# schematic.net
KiCad netlist of a schematic drawn in EasyEDA
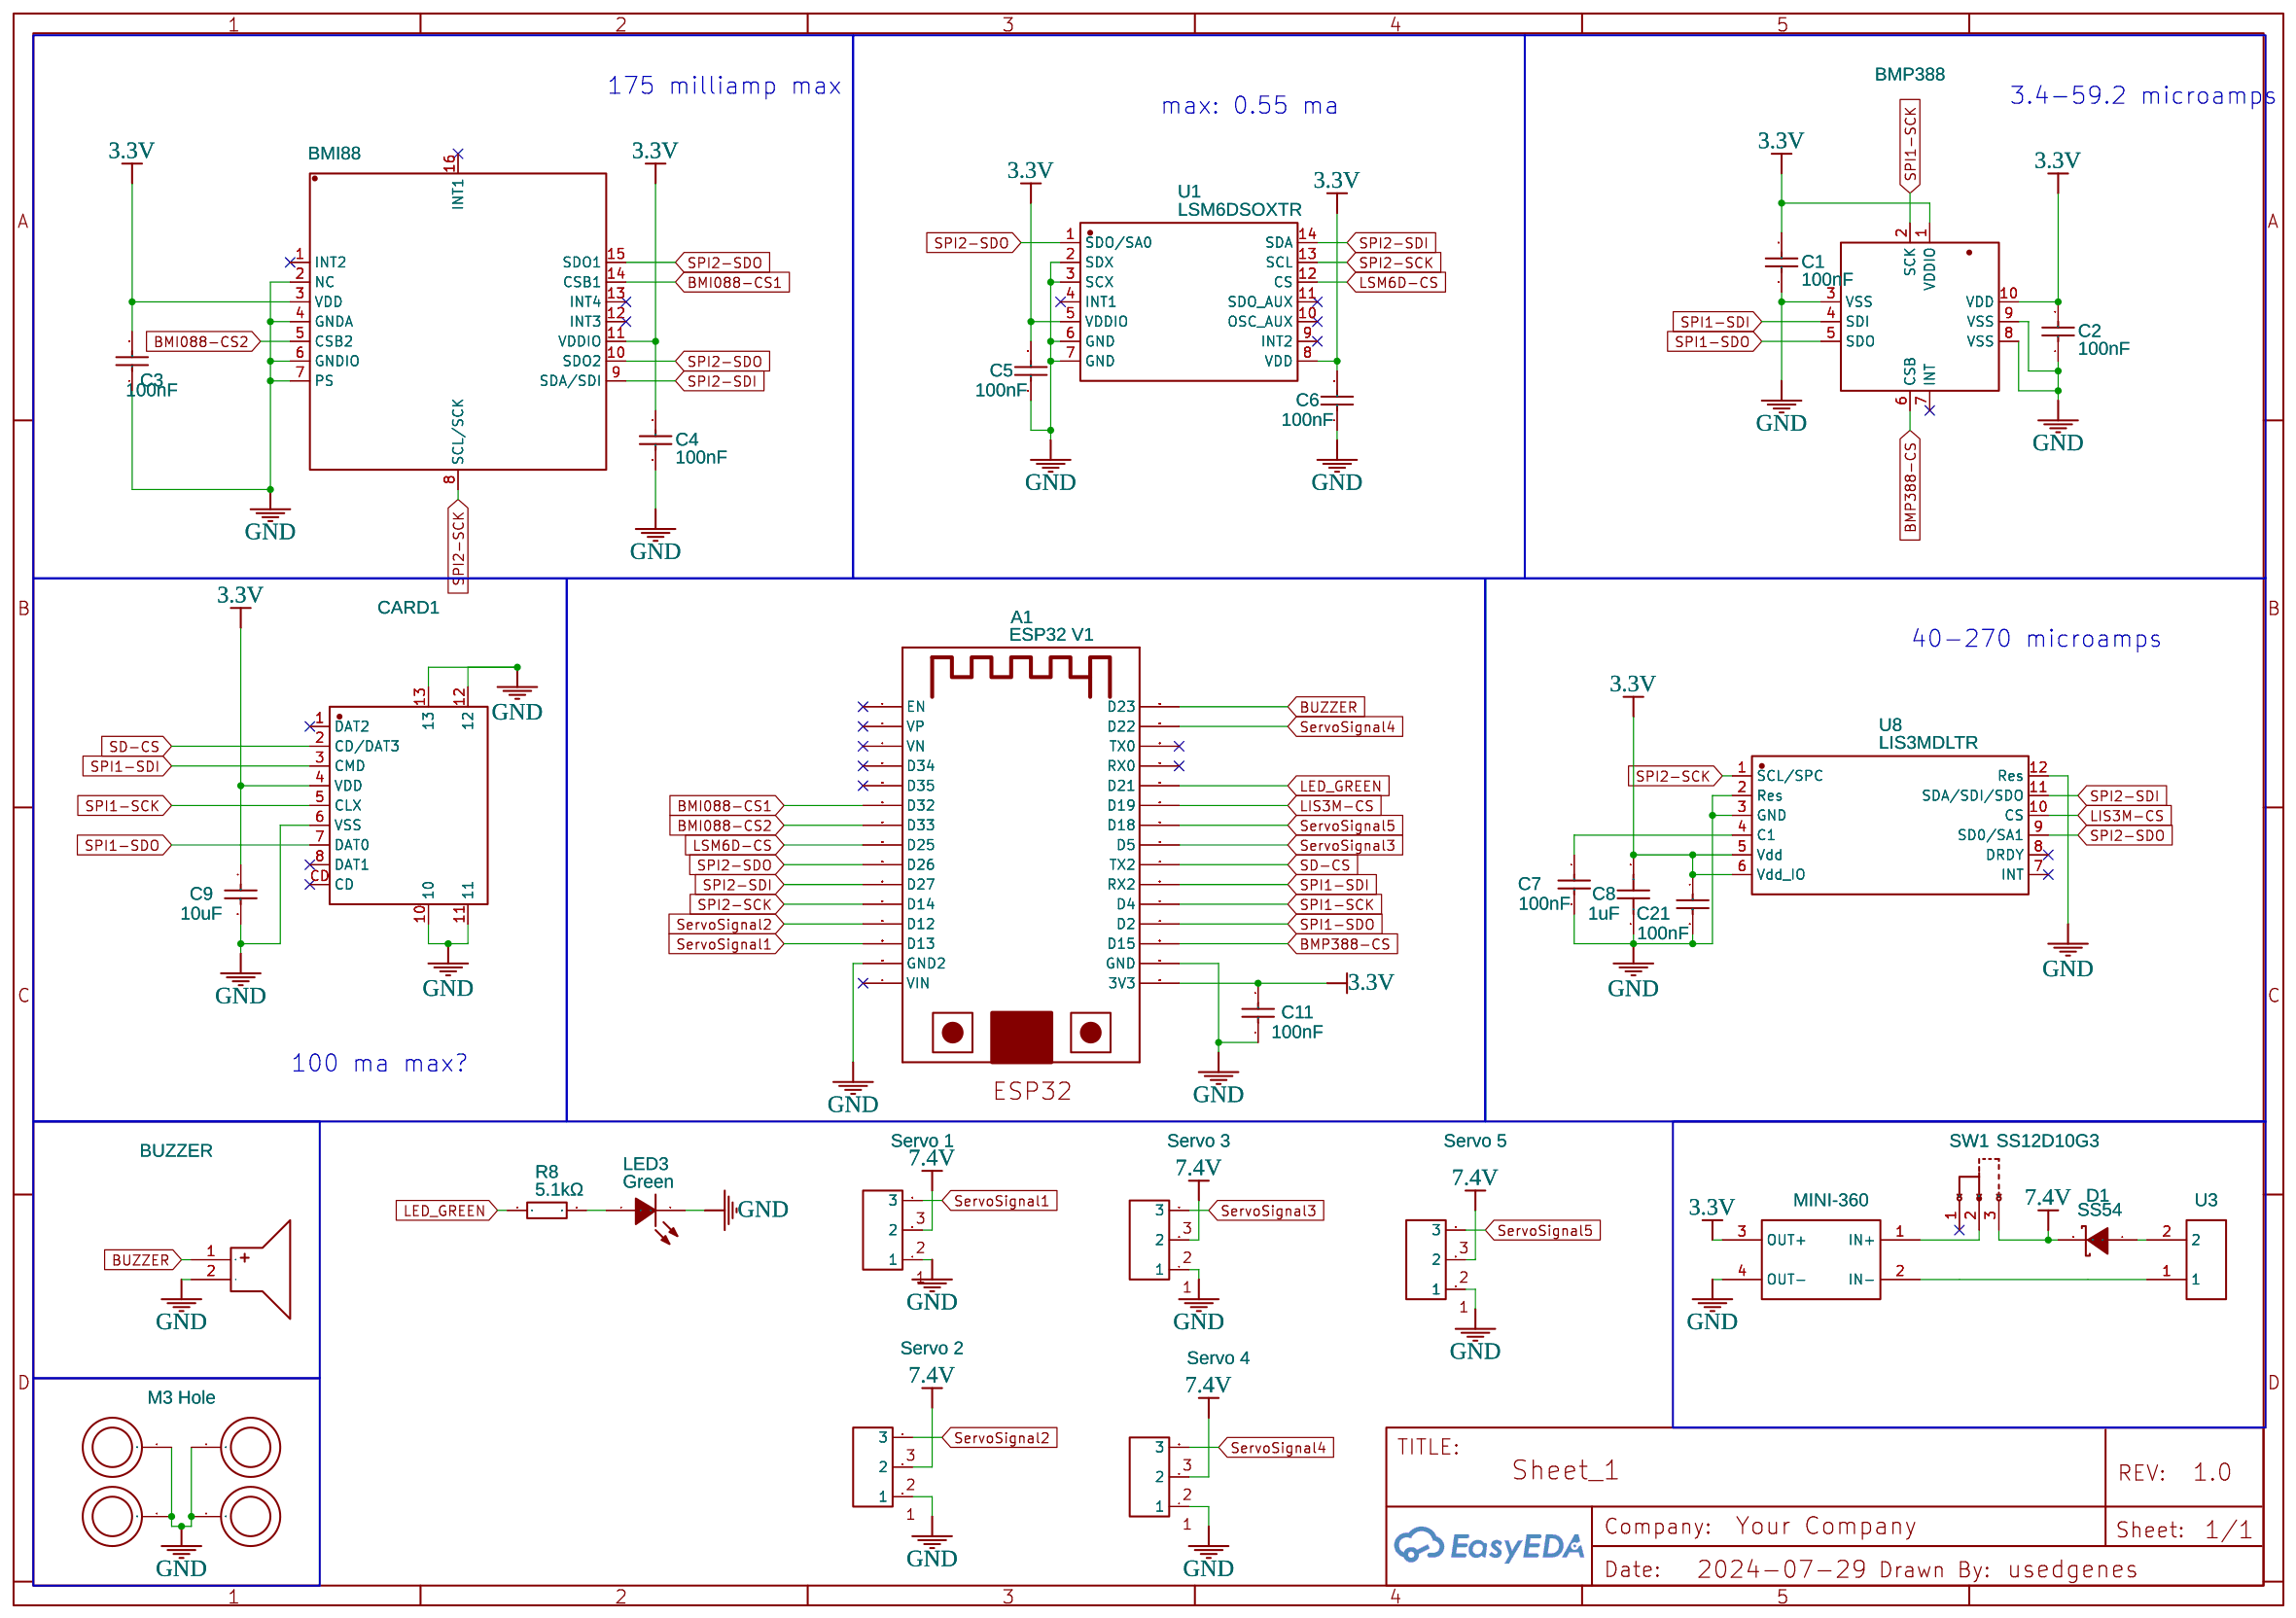
[diagram p0: schematic sheet]

(export (version "E")
  (design (tool "Eeschema 10.0.6"))
  (components
    (comp (ref "A1") (value "ESP32 V1") (libsource (lib "") (part "ESP32-DEVKIT-V1-30PIN")))
    (comp (ref "BMI88")
      (value "BMI088")
      (fields (field (name "Manufacturer") "Bosch(博世)"))
      (libsource (lib "") (part "BMI088"))
    )
    (comp (ref "BMP388")
      (value "BMP388")
      (fields (field (name "Manufacturer") "Bosch(博世)"))
      (libsource (lib "") (part "BMP388"))
    )
    (comp (ref "BUZZER")
      (value "4000Hz")
      (fields
        (field (name "Manufacturer Part") "SKY-1475-0540-45P7.6")
        (field (name "Manufacturer") "S&S(海旭)")
      )
      (libsource (lib "") (part "SKY-1475-0540-45P7.6"))
    )
    (comp (ref "C1")
      (value "100nF")
      (fields
        (field (name "Manufacturer Part") "CL05B104KO5NNNC")
        (field (name "Manufacturer") "SAMSUNG(三星)")
      )
      (libsource (lib "") (part "CL05B104KO5NNNC"))
    )
    (comp (ref "C2")
      (value "100nF")
      (fields
        (field (name "Manufacturer Part") "CL05B104KO5NNNC")
        (field (name "Manufacturer") "SAMSUNG(三星)")
      )
      (libsource (lib "") (part "CL05B104KO5NNNC"))
    )
    (comp (ref "C3")
      (value "100nF")
      (fields
        (field (name "Manufacturer Part") "CL05B104KO5NNNC")
        (field (name "Manufacturer") "SAMSUNG(三星)")
      )
      (libsource (lib "") (part "CL05B104KO5NNNC"))
    )
    (comp (ref "C4")
      (value "100nF")
      (fields
        (field (name "Manufacturer Part") "CL05B104KO5NNNC")
        (field (name "Manufacturer") "SAMSUNG(三星)")
      )
      (libsource (lib "") (part "CL05B104KO5NNNC"))
    )
    (comp (ref "C5")
      (value "100nF")
      (fields
        (field (name "Manufacturer Part") "CL05B104KO5NNNC")
        (field (name "Manufacturer") "SAMSUNG(三星)")
      )
      (libsource (lib "") (part "CL05B104KO5NNNC"))
    )
    (comp (ref "C6")
      (value "100nF")
      (fields
        (field (name "Manufacturer Part") "CL05B104KO5NNNC")
        (field (name "Manufacturer") "SAMSUNG(三星)")
      )
      (libsource (lib "") (part "CL05B104KO5NNNC"))
    )
    (comp (ref "C7")
      (value "100nF")
      (fields
        (field (name "Manufacturer Part") "CL05B104KO5NNNC")
        (field (name "Manufacturer") "SAMSUNG(三星)")
      )
      (libsource (lib "") (part "CL05B104KO5NNNC_1"))
    )
    (comp (ref "C8")
      (value "1uF")
      (fields
        (field (name "Manufacturer Part") "CL05A105KA5NQNC")
        (field (name "Manufacturer") "SAMSUNG(三星)")
      )
      (libsource (lib "") (part "CL05A105KA5NQNC"))
    )
    (comp (ref "C9")
      (value "10uF")
      (fields
        (field (name "Manufacturer Part") "CL05A106MQ5NUNC")
        (field (name "Manufacturer") "SAMSUNG(三星)")
      )
      (libsource (lib "") (part "CL05A106MQ5NUNC"))
    )
    (comp (ref "C11")
      (value "100nF")
      (fields
        (field (name "Manufacturer Part") "CL05B104KO5NNNC")
        (field (name "Manufacturer") "SAMSUNG(三星)")
      )
      (libsource (lib "") (part "CL05B104KO5NNNC"))
    )
    (comp (ref "C21")
      (value "100nF")
      (fields
        (field (name "Manufacturer Part") "CL05B104KO5NNNC")
        (field (name "Manufacturer") "SAMSUNG(三星)")
      )
      (libsource (lib "") (part "CL05B104KO5NNNC_1"))
    )
    (comp (ref "CARD1")
      (value "TF PUSH")
      (fields (field (name "Manufacturer") "SHOU HAN(首韩)"))
      (libsource (lib "") (part "TF PUSH"))
    )
    (comp (ref "D1")
      (value "SS54")
      (fields (field (name "Manufacturer") "MDD(辰达半导体)"))
      (libsource (lib "") (part "SS54_C22452"))
    )
    (comp (ref "H1") (value "M3 Hole") (libsource (lib "") (part "3MM_HOLE_1")))
    (comp (ref "H2") (value "3MM_HOLE") (libsource (lib "") (part "3MM_HOLE")))
    (comp (ref "H3") (value "3MM_HOLE") (libsource (lib "") (part "3MM_HOLE_1")))
    (comp (ref "H4") (value "3MM_HOLE") (libsource (lib "") (part "3MM_HOLE")))
    (comp (ref "LED3")
      (value "Green")
      (fields (field (name "Manufacturer Part") "KT-0805G") (field (name "Manufacturer") "KENTO"))
      (libsource (lib "") (part "0805G (Green)"))
    )
    (comp (ref "MINI-360") (value "MINI-360") (libsource (lib "") (part "MINI-360")))
    (comp (ref "P1")
      (value "Servo 2")
      (fields
        (field (name "Manufacturer Part") "Female headerHDR1X8-2.54")
        (field (name "Manufacturer") "BOOMELE")
      )
      (libsource (lib "") (part "HEADER PAD 3X RMM COPY"))
    )
    (comp (ref "P2")
      (value "Servo 1")
      (fields
        (field (name "Manufacturer Part") "Female headerHDR1X8-2.54")
        (field (name "Manufacturer") "BOOMELE")
      )
      (libsource (lib "") (part "HEADER PAD 3X RMM COPY"))
    )
    (comp (ref "P3")
      (value "Servo 3")
      (fields
        (field (name "Manufacturer Part") "Female headerHDR1X8-2.54")
        (field (name "Manufacturer") "BOOMELE")
      )
      (libsource (lib "") (part "HEADER PAD 3X RMM COPY"))
    )
    (comp (ref "P4")
      (value "Servo 5")
      (fields
        (field (name "Manufacturer Part") "Female headerHDR1X8-2.54")
        (field (name "Manufacturer") "BOOMELE")
      )
      (libsource (lib "") (part "HEADER PAD 3X RMM COPY"))
    )
    (comp (ref "P5")
      (value "Servo 4")
      (fields
        (field (name "Manufacturer Part") "Female headerHDR1X8-2.54")
        (field (name "Manufacturer") "BOOMELE")
      )
      (libsource (lib "") (part "HEADER PAD 3X RMM COPY"))
    )
    (comp (ref "R8")
      (value "5.1kΩ")
      (fields
        (field (name "Manufacturer Part") "0402WGF5101TCE")
        (field (name "Manufacturer") "UNI-ROYAL(厚声)")
      )
      (libsource (lib "") (part "0402WGF5101TCE"))
    )
    (comp (ref "SW1")
      (value "SS12D10G3")
      (fields (field (name "Manufacturer") "SHOU HAN(首韩)"))
      (libsource (lib "") (part "SS12D10G3"))
    )
    (comp (ref "U1")
      (value "LSM6DSOXTR")
      (fields (field (name "Manufacturer") "ST(意法半导体)"))
      (libsource (lib "") (part "LSM6DSOXTR"))
    )
    (comp (ref "U3") (value "Power Pins") (libsource (lib "") (part "1X2")))
    (comp (ref "U8")
      (value "LIS3MDLTR")
      (fields (field (name "Manufacturer") "ST(意法半导体)"))
      (libsource (lib "") (part "LIS3MDLTR"))
    )
  )
  (nets
    (net (code "1") (name "3.3V") (class "Default")
      (node (ref "A1") (pin "3V3") (pinfunction "3V3_3V3") (pintype "unspecified"))
      (node (ref "BMI88") (pin "11") (pinfunction "VDDIO_11") (pintype "unspecified"))
      (node (ref "BMI88") (pin "3") (pinfunction "VDD_3") (pintype "unspecified"))
      (node (ref "BMP388") (pin "1") (pinfunction "VDDIO_1") (pintype "unspecified"))
      (node (ref "BMP388") (pin "10") (pinfunction "VDD_10") (pintype "unspecified"))
      (node (ref "C1") (pin "2") (pinfunction "2_2") (pintype "input"))
      (node (ref "C11") (pin "2") (pinfunction "2_2") (pintype "input"))
      (node (ref "C2") (pin "2") (pinfunction "2_2") (pintype "input"))
      (node (ref "C21") (pin "1") (pinfunction "1_1") (pintype "input"))
      (node (ref "C3") (pin "2") (pinfunction "2_2") (pintype "input"))
      (node (ref "C4") (pin "2") (pinfunction "2_2") (pintype "input"))
      (node (ref "C5") (pin "2") (pinfunction "2_2") (pintype "input"))
      (node (ref "C6") (pin "2") (pinfunction "2_2") (pintype "input"))
      (node (ref "C8") (pin "2") (pinfunction "2_2") (pintype "unspecified"))
      (node (ref "C9") (pin "1") (pinfunction "1_1") (pintype "input"))
      (node (ref "CARD1") (pin "4") (pinfunction "VDD_4") (pintype "unspecified"))
      (node (ref "MINI-360") (pin "3") (pinfunction "OUT+_3") (pintype "unspecified"))
      (node (ref "U1") (pin "5") (pinfunction "VDDIO_5") (pintype "unspecified"))
      (node (ref "U1") (pin "8") (pinfunction "VDD_8") (pintype "unspecified"))
      (node (ref "U8") (pin "5") (pinfunction "Vdd_5") (pintype "unspecified"))
      (node (ref "U8") (pin "6") (pinfunction "Vdd_IO_6") (pintype "unspecified"))
    )
    (net (code "2") (name "7.4V") (class "Default")
      (node (ref "D1") (pin "2") (pinfunction "K_2") (pintype "unspecified"))
      (node (ref "P1") (pin "2") (pinfunction "2_2") (pintype "unspecified"))
      (node (ref "P2") (pin "2") (pinfunction "2_2") (pintype "unspecified"))
      (node (ref "P3") (pin "2") (pinfunction "2_2") (pintype "unspecified"))
      (node (ref "P4") (pin "2") (pinfunction "2_2") (pintype "unspecified"))
      (node (ref "P5") (pin "2") (pinfunction "2_2") (pintype "unspecified"))
      (node (ref "SW1") (pin "3") (pinfunction "3_3") (pintype "unspecified"))
    )
    (net (code "3") (name "BMI088-CS1") (class "Default")
      (node (ref "A1") (pin "D32") (pinfunction "D32_D32") (pintype "unspecified"))
      (node (ref "BMI88") (pin "14") (pinfunction "CSB1_14") (pintype "unspecified"))
    )
    (net (code "4") (name "BMI088-CS2") (class "Default")
      (node (ref "A1") (pin "D33") (pinfunction "D33_D33") (pintype "unspecified"))
      (node (ref "BMI88") (pin "5") (pinfunction "CSB2_5") (pintype "unspecified"))
    )
    (net (code "5") (name "BMP388-CS") (class "Default")
      (node (ref "A1") (pin "D15") (pinfunction "D15_D15") (pintype "unspecified"))
      (node (ref "BMP388") (pin "6") (pinfunction "CSB_6") (pintype "unspecified"))
    )
    (net (code "6") (name "BUZZER") (class "Default")
      (node (ref "A1") (pin "D23") (pinfunction "D23_D23") (pintype "unspecified"))
      (node (ref "BUZZER") (pin "1") (pinfunction "+_1") (pintype "unspecified"))
    )
    (net (code "7") (name "GND") (class "Default")
      (node (ref "A1") (pin "GND") (pinfunction "GND_GND") (pintype "unspecified"))
      (node (ref "A1") (pin "GND2") (pinfunction "GND2_GND2") (pintype "unspecified"))
      (node (ref "BMI88") (pin "2") (pinfunction "NC_2") (pintype "unspecified"))
      (node (ref "BMI88") (pin "4") (pinfunction "GNDA_4") (pintype "unspecified"))
      (node (ref "BMI88") (pin "6") (pinfunction "GNDIO_6") (pintype "unspecified"))
      (node (ref "BMI88") (pin "7") (pinfunction "PS_7") (pintype "unspecified"))
      (node (ref "BMP388") (pin "3") (pinfunction "VSS_3") (pintype "unspecified"))
      (node (ref "BMP388") (pin "8") (pinfunction "VSS_8") (pintype "unspecified"))
      (node (ref "BMP388") (pin "9") (pinfunction "VSS_9") (pintype "unspecified"))
      (node (ref "BUZZER") (pin "2") (pinfunction "-_2") (pintype "unspecified"))
      (node (ref "C1") (pin "1") (pinfunction "1_1") (pintype "input"))
      (node (ref "C11") (pin "1") (pinfunction "1_1") (pintype "input"))
      (node (ref "C2") (pin "1") (pinfunction "1_1") (pintype "input"))
      (node (ref "C21") (pin "2") (pinfunction "2_2") (pintype "input"))
      (node (ref "C3") (pin "1") (pinfunction "1_1") (pintype "input"))
      (node (ref "C4") (pin "1") (pinfunction "1_1") (pintype "input"))
      (node (ref "C5") (pin "1") (pinfunction "1_1") (pintype "input"))
      (node (ref "C6") (pin "1") (pinfunction "1_1") (pintype "input"))
      (node (ref "C7") (pin "2") (pinfunction "2_2") (pintype "input"))
      (node (ref "C8") (pin "1") (pinfunction "1_1") (pintype "unspecified"))
      (node (ref "C9") (pin "2") (pinfunction "2_2") (pintype "input"))
      (node (ref "CARD1") (pin "10") (pinfunction "10_10") (pintype "unspecified"))
      (node (ref "CARD1") (pin "11") (pinfunction "11_11") (pintype "unspecified"))
      (node (ref "CARD1") (pin "12") (pinfunction "12_12") (pintype "unspecified"))
      (node (ref "CARD1") (pin "13") (pinfunction "13_13") (pintype "unspecified"))
      (node (ref "CARD1") (pin "6") (pinfunction "VSS_6") (pintype "unspecified"))
      (node (ref "H1") (pin "1") (pinfunction "1_1") (pintype "bidirectional"))
      (node (ref "H2") (pin "1") (pinfunction "1_1") (pintype "bidirectional"))
      (node (ref "H3") (pin "1") (pinfunction "1_1") (pintype "bidirectional"))
      (node (ref "H4") (pin "1") (pinfunction "1_1") (pintype "bidirectional"))
      (node (ref "LED3") (pin "2") (pinfunction "K_2") (pintype "unspecified"))
      (node (ref "MINI-360") (pin "4") (pinfunction "OUT-_4") (pintype "unspecified"))
      (node (ref "P1") (pin "1") (pinfunction "1_1") (pintype "unspecified"))
      (node (ref "P2") (pin "1") (pinfunction "1_1") (pintype "unspecified"))
      (node (ref "P3") (pin "1") (pinfunction "1_1") (pintype "unspecified"))
      (node (ref "P4") (pin "1") (pinfunction "1_1") (pintype "unspecified"))
      (node (ref "P5") (pin "1") (pinfunction "1_1") (pintype "unspecified"))
      (node (ref "U1") (pin "2") (pinfunction "SDX_2") (pintype "unspecified"))
      (node (ref "U1") (pin "3") (pinfunction "SCX_3") (pintype "unspecified"))
      (node (ref "U1") (pin "6") (pinfunction "GND_6") (pintype "unspecified"))
      (node (ref "U1") (pin "7") (pinfunction "GND_7") (pintype "unspecified"))
      (node (ref "U8") (pin "12") (pinfunction "Res_12") (pintype "unspecified"))
      (node (ref "U8") (pin "2") (pinfunction "Res_2") (pintype "unspecified"))
      (node (ref "U8") (pin "3") (pinfunction "GND_3") (pintype "unspecified"))
    )
    (net (code "8") (name "LED_GREEN") (class "Default")
      (node (ref "A1") (pin "D21") (pinfunction "D21_D21") (pintype "unspecified"))
      (node (ref "R8") (pin "1") (pinfunction "1_1") (pintype "input"))
    )
    (net (code "9") (name "LIS3M-CS") (class "Default")
      (node (ref "A1") (pin "D19") (pinfunction "D19_D19") (pintype "unspecified"))
      (node (ref "U8") (pin "10") (pinfunction "CS_10") (pintype "unspecified"))
    )
    (net (code "10") (name "LSM6D-CS") (class "Default")
      (node (ref "A1") (pin "D25") (pinfunction "D25_D25") (pintype "unspecified"))
      (node (ref "U1") (pin "12") (pinfunction "CS_12") (pintype "unspecified"))
    )
    (net (code "11") (name "Net-(D1-A)") (class "Default")
      (node (ref "D1") (pin "1") (pinfunction "A_1") (pintype "unspecified"))
      (node (ref "U3") (pin "2") (pinfunction "2_2") (pintype "unspecified"))
    )
    (net (code "12") (name "Net-(LED3-A)") (class "Default")
      (node (ref "LED3") (pin "1") (pinfunction "A_1") (pintype "unspecified"))
      (node (ref "R8") (pin "2") (pinfunction "2_2") (pintype "input"))
    )
    (net (code "13") (name "Net-(MINI-360-IN+)") (class "Default")
      (node (ref "MINI-360") (pin "1") (pinfunction "IN+_1") (pintype "unspecified"))
      (node (ref "SW1") (pin "2") (pinfunction "2_2") (pintype "unspecified"))
    )
    (net (code "14") (name "Net-(MINI-360-IN-)") (class "Default")
      (node (ref "MINI-360") (pin "2") (pinfunction "IN-_2") (pintype "unspecified"))
      (node (ref "U3") (pin "1") (pinfunction "1_1") (pintype "unspecified"))
    )
    (net (code "15") (name "Net-(U8-C1)") (class "Default")
      (node (ref "C7") (pin "1") (pinfunction "1_1") (pintype "input"))
      (node (ref "U8") (pin "4") (pinfunction "C1_4") (pintype "unspecified"))
    )
    (net (code "16") (name "SD-CS") (class "Default")
      (node (ref "A1") (pin "TX2") (pinfunction "TX2_TX2") (pintype "unspecified"))
      (node (ref "CARD1") (pin "2") (pinfunction "CD/DAT3_2") (pintype "unspecified"))
    )
    (net (code "17") (name "SPI1-SCK") (class "Default")
      (node (ref "A1") (pin "D4") (pinfunction "D4_D4") (pintype "unspecified"))
      (node (ref "BMP388") (pin "2") (pinfunction "SCK_2") (pintype "unspecified"))
      (node (ref "CARD1") (pin "5") (pinfunction "CLX_5") (pintype "unspecified"))
    )
    (net (code "18") (name "SPI1-SDI") (class "Default")
      (node (ref "A1") (pin "RX2") (pinfunction "RX2_RX2") (pintype "unspecified"))
      (node (ref "BMP388") (pin "4") (pinfunction "SDI_4") (pintype "unspecified"))
      (node (ref "CARD1") (pin "3") (pinfunction "CMD_3") (pintype "unspecified"))
    )
    (net (code "19") (name "SPI1-SDO") (class "Default")
      (node (ref "A1") (pin "D2") (pinfunction "D2_D2") (pintype "unspecified"))
      (node (ref "BMP388") (pin "5") (pinfunction "SDO_5") (pintype "unspecified"))
      (node (ref "CARD1") (pin "7") (pinfunction "DAT0_7") (pintype "unspecified"))
    )
    (net (code "20") (name "SPI2-SCK") (class "Default")
      (node (ref "A1") (pin "D14") (pinfunction "D14_D14") (pintype "unspecified"))
      (node (ref "BMI88") (pin "8") (pinfunction "SCL/SCK_8") (pintype "unspecified"))
      (node (ref "U1") (pin "13") (pinfunction "SCL_13") (pintype "unspecified"))
      (node (ref "U8") (pin "1") (pinfunction "SCL/SPC_1") (pintype "unspecified"))
    )
    (net (code "21") (name "SPI2-SDI") (class "Default")
      (node (ref "A1") (pin "D27") (pinfunction "D27_D27") (pintype "unspecified"))
      (node (ref "BMI88") (pin "9") (pinfunction "SDA/SDI_9") (pintype "unspecified"))
      (node (ref "U1") (pin "14") (pinfunction "SDA_14") (pintype "unspecified"))
      (node (ref "U8") (pin "11") (pinfunction "SDA/SDI/SDO_11") (pintype "unspecified"))
    )
    (net (code "22") (name "SPI2-SDO") (class "Default")
      (node (ref "A1") (pin "D26") (pinfunction "D26_D26") (pintype "unspecified"))
      (node (ref "BMI88") (pin "10") (pinfunction "SDO2_10") (pintype "unspecified"))
      (node (ref "BMI88") (pin "15") (pinfunction "SDO1_15") (pintype "unspecified"))
      (node (ref "U1") (pin "1") (pinfunction "SDO/SA0_1") (pintype "unspecified"))
      (node (ref "U8") (pin "9") (pinfunction "SD0/SA1_9") (pintype "unspecified"))
    )
    (net (code "23") (name "ServoSignal1") (class "Default")
      (node (ref "A1") (pin "D13") (pinfunction "D13_D13") (pintype "unspecified"))
      (node (ref "P2") (pin "3") (pinfunction "3_3") (pintype "unspecified"))
    )
    (net (code "24") (name "ServoSignal2") (class "Default")
      (node (ref "A1") (pin "D12") (pinfunction "D12_D12") (pintype "unspecified"))
      (node (ref "P1") (pin "3") (pinfunction "3_3") (pintype "unspecified"))
    )
    (net (code "25") (name "ServoSignal3") (class "Default")
      (node (ref "A1") (pin "D5") (pinfunction "D5_D5") (pintype "unspecified"))
      (node (ref "P3") (pin "3") (pinfunction "3_3") (pintype "unspecified"))
    )
    (net (code "26") (name "ServoSignal4") (class "Default")
      (node (ref "A1") (pin "D22") (pinfunction "D22_D22") (pintype "unspecified"))
      (node (ref "P5") (pin "3") (pinfunction "3_3") (pintype "unspecified"))
    )
    (net (code "27") (name "ServoSignal5") (class "Default")
      (node (ref "A1") (pin "D18") (pinfunction "D18_D18") (pintype "unspecified"))
      (node (ref "P4") (pin "3") (pinfunction "3_3") (pintype "unspecified"))
    )
    (net (code "28") (name "unconnected-(A1-PadD34)") (class "Default")
      (node (ref "A1") (pin "D34") (pinfunction "D34_D34") (pintype "unspecified+no_connect"))
    )
    (net (code "29") (name "unconnected-(A1-PadD35)") (class "Default")
      (node (ref "A1") (pin "D35") (pinfunction "D35_D35") (pintype "unspecified+no_connect"))
    )
    (net (code "30") (name "unconnected-(A1-PadEN)") (class "Default")
      (node (ref "A1") (pin "EN") (pinfunction "EN_EN") (pintype "unspecified+no_connect"))
    )
    (net (code "31") (name "unconnected-(A1-PadRX0)") (class "Default")
      (node (ref "A1") (pin "RX0") (pinfunction "RX0_RX0") (pintype "unspecified+no_connect"))
    )
    (net (code "32") (name "unconnected-(A1-PadTX0)") (class "Default")
      (node (ref "A1") (pin "TX0") (pinfunction "TX0_TX0") (pintype "unspecified+no_connect"))
    )
    (net (code "33") (name "unconnected-(A1-PadVIN)") (class "Default")
      (node (ref "A1") (pin "VIN") (pinfunction "VIN_VIN") (pintype "unspecified+no_connect"))
    )
    (net (code "34") (name "unconnected-(A1-PadVN)") (class "Default")
      (node (ref "A1") (pin "VN") (pinfunction "VN_VN") (pintype "unspecified+no_connect"))
    )
    (net (code "35") (name "unconnected-(A1-PadVP)") (class "Default")
      (node (ref "A1") (pin "VP") (pinfunction "VP_VP") (pintype "unspecified+no_connect"))
    )
    (net (code "36") (name "unconnected-(BMI88-INT1-Pad16)") (class "Default")
      (node (ref "BMI88") (pin "16") (pinfunction "INT1_16") (pintype "unspecified+no_connect"))
    )
    (net (code "37") (name "unconnected-(BMI88-INT2-Pad1)") (class "Default")
      (node (ref "BMI88") (pin "1") (pinfunction "INT2_1") (pintype "unspecified+no_connect"))
    )
    (net (code "38") (name "unconnected-(BMI88-INT3-Pad12)") (class "Default")
      (node (ref "BMI88") (pin "12") (pinfunction "INT3_12") (pintype "unspecified+no_connect"))
    )
    (net (code "39") (name "unconnected-(BMI88-INT4-Pad13)") (class "Default")
      (node (ref "BMI88") (pin "13") (pinfunction "INT4_13") (pintype "unspecified+no_connect"))
    )
    (net (code "40") (name "unconnected-(BMP388-INT-Pad7)") (class "Default")
      (node (ref "BMP388") (pin "7") (pinfunction "INT_7") (pintype "unspecified+no_connect"))
    )
    (net (code "41") (name "unconnected-(CARD1-DAT1-Pad8)") (class "Default")
      (node (ref "CARD1") (pin "8") (pinfunction "DAT1_8") (pintype "unspecified+no_connect"))
    )
    (net (code "42") (name "unconnected-(CARD1-DAT2-Pad1)") (class "Default")
      (node (ref "CARD1") (pin "1") (pinfunction "DAT2_1") (pintype "unspecified+no_connect"))
    )
    (net (code "43") (name "unconnected-(CARD1-PadCD)") (class "Default")
      (node (ref "CARD1") (pin "CD") (pinfunction "CD_CD") (pintype "unspecified+no_connect"))
    )
    (net (code "44") (name "unconnected-(SW1-Pad1)") (class "Default")
      (node (ref "SW1") (pin "1") (pinfunction "1_1") (pintype "unspecified+no_connect"))
    )
    (net (code "45") (name "unconnected-(U1-INT1-Pad4)") (class "Default")
      (node (ref "U1") (pin "4") (pinfunction "INT1_4") (pintype "unspecified+no_connect"))
    )
    (net (code "46") (name "unconnected-(U1-INT2-Pad9)") (class "Default")
      (node (ref "U1") (pin "9") (pinfunction "INT2_9") (pintype "unspecified+no_connect"))
    )
    (net (code "47") (name "unconnected-(U1-OSC_AUX-Pad10)") (class "Default")
      (node (ref "U1") (pin "10") (pinfunction "OSC_AUX_10") (pintype "unspecified+no_connect"))
    )
    (net (code "48") (name "unconnected-(U1-SDO_AUX-Pad11)") (class "Default")
      (node (ref "U1") (pin "11") (pinfunction "SDO_AUX_11") (pintype "unspecified+no_connect"))
    )
    (net (code "49") (name "unconnected-(U8-DRDY-Pad8)") (class "Default")
      (node (ref "U8") (pin "8") (pinfunction "DRDY_8") (pintype "unspecified+no_connect"))
    )
    (net (code "50") (name "unconnected-(U8-INT-Pad7)") (class "Default")
      (node (ref "U8") (pin "7") (pinfunction "INT_7") (pintype "unspecified+no_connect"))
    )
  )
)
